# board.net
KiCad netlist of a schematic drawn in EAGLE
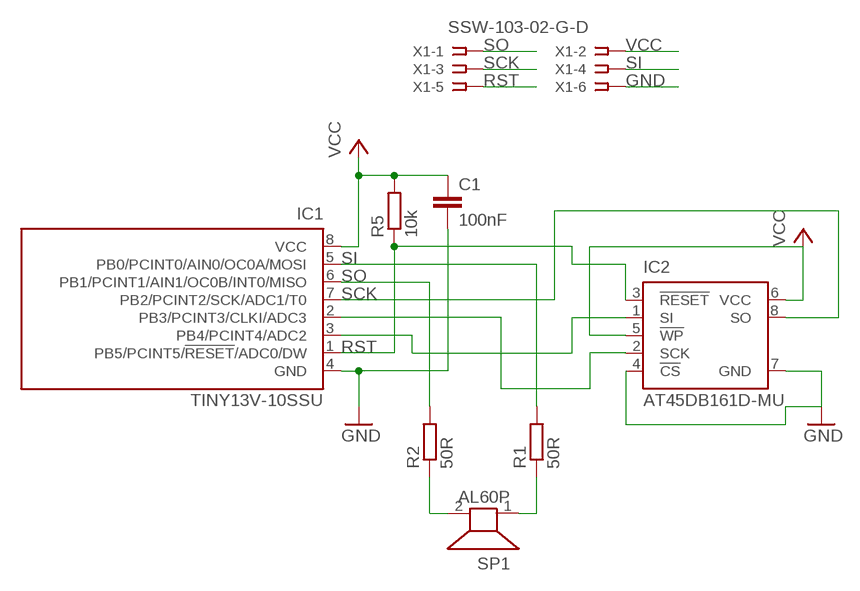
[diagram p0: schematic, sheet 1]

(export (version "E")
  (design (tool "Eeschema 10.0.6"))
  (components
    (comp (ref "C1")
      (value "100nF")
      (footprint "eagle-import:C1206K")
      (libsource (lib "eagle-import") (part "C-EUC1206K"))
    )
    (comp (ref "IC1")
      (value "TINY13V-10SSU")
      (footprint "eagle-import:8S1")
      (fields (field (name "MPN") "ATTINY13V-10SSU"))
      (libsource (lib "eagle-import") (part "TINY13SSUV-10"))
    )
    (comp (ref "IC2")
      (value "AT45DB161D-MU")
      (footprint "eagle-import:VDFN-8")
      (fields (field (name "MF") "ATMEL") (field (name "MPN") "AT45DB161D-SU"))
      (libsource (lib "eagle-import") (part "AT45DB161D-MU"))
    )
    (comp (ref "R1")
      (value "50R")
      (footprint "eagle-import:0204_5")
      (libsource (lib "eagle-import") (part "R-EU_0204/5"))
    )
    (comp (ref "R2")
      (value "50R")
      (footprint "eagle-import:0204_5")
      (libsource (lib "eagle-import") (part "R-EU_0204/5"))
    )
    (comp (ref "R5")
      (value "10k")
      (footprint "eagle-import:0204_5")
      (libsource (lib "eagle-import") (part "R-EU_0204/5"))
    )
    (comp (ref "SP1")
      (value "AL60P")
      (footprint "eagle-import:AL60P")
      (libsource (lib "eagle-import") (part "AL60P"))
    )
    (comp (ref "X1")
      (value "SSW-103-02-G-D")
      (footprint "eagle-import:SSW-103-02-G-D")
      (fields (field (name "MF") "Samtec Inc."))
      (libsource (lib "eagle-import") (part "SSW-103-02-G-D"))
    )
  )
  (nets
    (net (code "1") (name "/RST") (class "Default")
      (node (ref "IC1") (pin "1") (pinfunction "PB5/PCINT5/~{RESET}/ADC0/DW_1") (pintype "bidirectional"))
      (node (ref "IC2") (pin "3") (pinfunction "~{RESET}_3") (pintype "input"))
      (node (ref "R5") (pin "1") (pinfunction "1_1") (pintype "passive"))
      (node (ref "X1") (pin "5") (pinfunction "1_5") (pintype "passive"))
    )
    (net (code "2") (name "/SCK") (class "Default")
      (node (ref "IC1") (pin "7") (pinfunction "PB2/PCINT2/SCK/ADC1/T0_7") (pintype "bidirectional"))
      (node (ref "IC2") (pin "8") (pinfunction "SO_8") (pintype "output"))
      (node (ref "X1") (pin "3") (pinfunction "1_3") (pintype "passive"))
    )
    (net (code "3") (name "/SI") (class "Default")
      (node (ref "IC1") (pin "5") (pinfunction "PB0/PCINT0/AIN0/OC0A/MOSI_5") (pintype "bidirectional"))
      (node (ref "R1") (pin "2") (pinfunction "2_2") (pintype "passive"))
      (node (ref "X1") (pin "4") (pinfunction "1_4") (pintype "passive"))
    )
    (net (code "4") (name "/SO") (class "Default")
      (node (ref "IC1") (pin "6") (pinfunction "PB1/PCINT1/AIN1/OC0B/INT0/MISO_6") (pintype "bidirectional"))
      (node (ref "R2") (pin "2") (pinfunction "2_2") (pintype "passive"))
      (node (ref "X1") (pin "1") (pinfunction "1_1") (pintype "passive"))
    )
    (net (code "5") (name "GND") (class "Default")
      (node (ref "C1") (pin "2") (pinfunction "2_2") (pintype "passive"))
      (node (ref "IC1") (pin "4") (pinfunction "GND_4") (pintype "power_in"))
      (node (ref "IC2") (pin "4") (pinfunction "~{CS}_4") (pintype "input"))
      (node (ref "IC2") (pin "7") (pinfunction "GND_7") (pintype "power_in"))
      (node (ref "X1") (pin "6") (pinfunction "1_6") (pintype "passive"))
    )
    (net (code "6") (name "Net-(IC1-PB3{slash}PCINT3{slash}CLKI{slash}ADC3)") (class "Default")
      (node (ref "IC1") (pin "2") (pinfunction "PB3/PCINT3/CLKI/ADC3_2") (pintype "bidirectional"))
      (node (ref "IC2") (pin "2") (pinfunction "SCK_2") (pintype "input"))
    )
    (net (code "7") (name "Net-(IC1-PB4{slash}PCINT4{slash}ADC2)") (class "Default")
      (node (ref "IC1") (pin "3") (pinfunction "PB4/PCINT4/ADC2_3") (pintype "bidirectional"))
      (node (ref "IC2") (pin "1") (pinfunction "SI_1") (pintype "input"))
    )
    (net (code "8") (name "Net-(R1-Pad1)") (class "Default")
      (node (ref "R1") (pin "1") (pinfunction "1_1") (pintype "passive"))
      (node (ref "SP1") (pin "1") (pinfunction "1_1") (pintype "passive"))
    )
    (net (code "9") (name "Net-(R2-Pad1)") (class "Default")
      (node (ref "R2") (pin "1") (pinfunction "1_1") (pintype "passive"))
      (node (ref "SP1") (pin "2") (pinfunction "2_2") (pintype "passive"))
    )
    (net (code "10") (name "VCC") (class "Default")
      (node (ref "C1") (pin "1") (pinfunction "1_1") (pintype "passive"))
      (node (ref "IC1") (pin "8") (pinfunction "VCC_8") (pintype "power_in"))
      (node (ref "IC2") (pin "5") (pinfunction "~{WP}_5") (pintype "input"))
      (node (ref "IC2") (pin "6") (pinfunction "VCC_6") (pintype "power_in"))
      (node (ref "R5") (pin "2") (pinfunction "2_2") (pintype "passive"))
      (node (ref "X1") (pin "2") (pinfunction "1_2") (pintype "passive"))
    )
  )
)
